# 4__Output_Feedback_2.net
KiCad netlist of a schematic drawn in Altium Designer
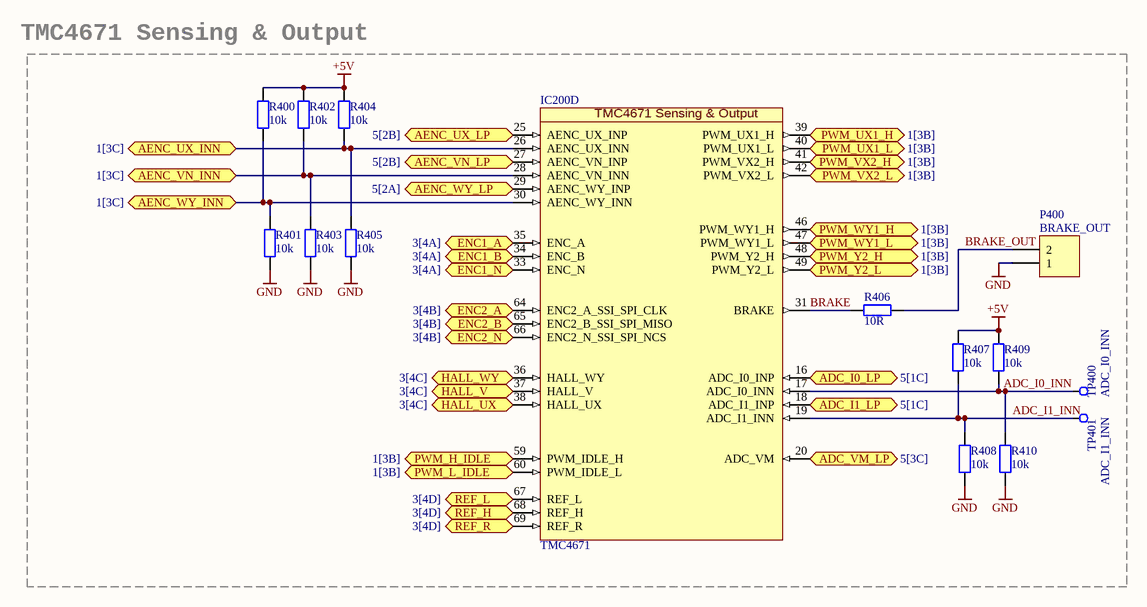
[diagram p0: [4]_Output_Feedback_2.SchDoc]

(export (version "E")
  (design (tool "Eeschema 10.0.6"))
  (components
    (comp (ref "IC200")
      (value "TMC4671")
      (footprint "QFN40P1050X650X90_HS-77N")
      (fields (field (name "MF") "TRINAMIC"))
      (libsource (lib "TMC4671-EVAL_V1_0") (part "TMC4671"))
    )
    (comp (ref "P400")
      (value "BRAKE_OUT")
      (footprint "TH_HDR_1X2")
      (description "Header, 2-Pin")
      (libsource (lib "Miscellaneous Connectors") (part "Header 2"))
    )
    (comp (ref "R400")
      (value "10k")
      (footprint "R0603")
      (description "SMD Chip Resistor, Thick Film, 10 kohm, 50 V, 0603 [1608 Metric], 63 mW, ± 1%, MC Series")
      (fields
        (field (name "MPN") "MC0063W0603110K")
        (field (name "MF") "MULTICOMP")
        (field (name "RESISTANCE") "10k")
      )
      (libsource (lib "SMD_Passives") (part "R, 10 kohm, 50 V, 0603 [1608 Metric], 63 mW, ± 1%, MC Series"))
    )
    (comp (ref "R401")
      (value "10k")
      (footprint "R0603")
      (description "SMD Chip Resistor, Thick Film, 10 kohm, 50 V, 0603 [1608 Metric], 63 mW, ± 1%, MC Series")
      (fields
        (field (name "MPN") "MC0063W0603110K")
        (field (name "MF") "MULTICOMP")
        (field (name "RESISTANCE") "10k")
      )
      (libsource (lib "SMD_Passives") (part "R, 10 kohm, 50 V, 0603 [1608 Metric], 63 mW, ± 1%, MC Series"))
    )
    (comp (ref "R402")
      (value "10k")
      (footprint "R0603")
      (description "SMD Chip Resistor, Thick Film, 10 kohm, 50 V, 0603 [1608 Metric], 63 mW, ± 1%, MC Series")
      (fields
        (field (name "MPN") "MC0063W0603110K")
        (field (name "MF") "MULTICOMP")
        (field (name "RESISTANCE") "10k")
      )
      (libsource (lib "SMD_Passives") (part "R, 10 kohm, 50 V, 0603 [1608 Metric], 63 mW, ± 1%, MC Series"))
    )
    (comp (ref "R403")
      (value "10k")
      (footprint "R0603")
      (description "SMD Chip Resistor, Thick Film, 10 kohm, 50 V, 0603 [1608 Metric], 63 mW, ± 1%, MC Series")
      (fields
        (field (name "MPN") "MC0063W0603110K")
        (field (name "MF") "MULTICOMP")
        (field (name "RESISTANCE") "10k")
      )
      (libsource (lib "SMD_Passives") (part "R, 10 kohm, 50 V, 0603 [1608 Metric], 63 mW, ± 1%, MC Series"))
    )
    (comp (ref "R404")
      (value "10k")
      (footprint "R0603")
      (description "SMD Chip Resistor, Thick Film, 10 kohm, 50 V, 0603 [1608 Metric], 63 mW, ± 1%, MC Series")
      (fields
        (field (name "MPN") "MC0063W0603110K")
        (field (name "MF") "MULTICOMP")
        (field (name "RESISTANCE") "10k")
      )
      (libsource (lib "SMD_Passives") (part "R, 10 kohm, 50 V, 0603 [1608 Metric], 63 mW, ± 1%, MC Series"))
    )
    (comp (ref "R405")
      (value "10k")
      (footprint "R0603")
      (description "SMD Chip Resistor, Thick Film, 10 kohm, 50 V, 0603 [1608 Metric], 63 mW, ± 1%, MC Series")
      (fields
        (field (name "MPN") "MC0063W0603110K")
        (field (name "MF") "MULTICOMP")
        (field (name "RESISTANCE") "10k")
      )
      (libsource (lib "SMD_Passives") (part "R, 10 kohm, 50 V, 0603 [1608 Metric], 63 mW, ± 1%, MC Series"))
    )
    (comp (ref "R406")
      (value "10R")
      (footprint "R0603")
      (description "SMD Chip Resistor, Thick Film, 10 ohm, 50 V, 0603 [1608 Metric], 100 mW, ± 1%, MCWR Series")
      (fields
        (field (name "MPN") "MC0063W0603110K")
        (field (name "MF") "MULTICOMP")
        (field (name "RESISTANCE") "10R")
      )
      (libsource (lib "SMD_Passives") (part "R, 10 ohm, 50 V, 0603 [1608 Metric], 100 mW, ± 1%, MCWR Series"))
    )
    (comp (ref "R407")
      (value "10k")
      (footprint "R0603")
      (description "SMD Chip Resistor, Thick Film, 10 kohm, 50 V, 0603 [1608 Metric], 63 mW, ± 1%, MC Series")
      (fields
        (field (name "MPN") "MC0063W0603110K")
        (field (name "MF") "MULTICOMP")
        (field (name "RESISTANCE") "10k")
      )
      (libsource (lib "SMD_Passives") (part "R, 10 kohm, 50 V, 0603 [1608 Metric], 63 mW, ± 1%, MC Series"))
    )
    (comp (ref "R408")
      (value "10k")
      (footprint "R0603")
      (description "SMD Chip Resistor, Thick Film, 10 kohm, 50 V, 0603 [1608 Metric], 63 mW, ± 1%, MC Series")
      (fields
        (field (name "MPN") "MC0063W0603110K")
        (field (name "MF") "MULTICOMP")
        (field (name "RESISTANCE") "10k")
      )
      (libsource (lib "SMD_Passives") (part "R, 10 kohm, 50 V, 0603 [1608 Metric], 63 mW, ± 1%, MC Series"))
    )
    (comp (ref "R409")
      (value "10k")
      (footprint "R0603")
      (description "SMD Chip Resistor, Thick Film, 10 kohm, 50 V, 0603 [1608 Metric], 63 mW, ± 1%, MC Series")
      (fields
        (field (name "MPN") "MC0063W0603110K")
        (field (name "MF") "MULTICOMP")
        (field (name "RESISTANCE") "10k")
      )
      (libsource (lib "SMD_Passives") (part "R, 10 kohm, 50 V, 0603 [1608 Metric], 63 mW, ± 1%, MC Series"))
    )
    (comp (ref "R410")
      (value "10k")
      (footprint "R0603")
      (description "SMD Chip Resistor, Thick Film, 10 kohm, 50 V, 0603 [1608 Metric], 63 mW, ± 1%, MC Series")
      (fields
        (field (name "MPN") "MC0063W0603110K")
        (field (name "MF") "MULTICOMP")
        (field (name "RESISTANCE") "10k")
      )
      (libsource (lib "SMD_Passives") (part "R, 10 kohm, 50 V, 0603 [1608 Metric], 63 mW, ± 1%, MC Series"))
    )
    (comp (ref "TP400")
      (value "ADC_I0_INN")
      (footprint "TP_SMD_1.2MM_ROUND")
      (description "SMD testpoint, 1.2mm pad, round")
      (libsource (lib "TMC-EVAL_TMPL_V1_0") (part "TP_SMD_Xmm"))
    )
    (comp (ref "TP401")
      (value "ADC_I1_INN")
      (footprint "TP_SMD_1.2MM_ROUND")
      (description "SMD testpoint, 1.2mm pad, round")
      (libsource (lib "TMC-EVAL_TMPL_V1_0") (part "TP_SMD_Xmm"))
    )
  )
  (nets
    (net (code "1") (name "+5V") (class "Default")
      (node (ref "R400") (pin "2") (pinfunction "2_2") (pintype "passive"))
      (node (ref "R402") (pin "2") (pinfunction "2_2") (pintype "passive"))
      (node (ref "R404") (pin "2") (pinfunction "2_2") (pintype "passive"))
      (node (ref "R407") (pin "2") (pinfunction "2_2") (pintype "passive"))
      (node (ref "R409") (pin "2") (pinfunction "2_2") (pintype "passive"))
    )
    (net (code "2") (name "/ADC_I0_INN") (class "Default")
      (node (ref "IC200") (pin "17") (pinfunction "ADC_I0_INN_17") (pintype "input"))
      (node (ref "R409") (pin "1") (pinfunction "1_1") (pintype "passive"))
      (node (ref "R410") (pin "2") (pinfunction "2_2") (pintype "passive"))
      (node (ref "TP400") (pin "1") (pinfunction "1_1") (pintype "passive"))
    )
    (net (code "3") (name "/ADC_I0_LP") (class "Default")
      (node (ref "IC200") (pin "16") (pinfunction "ADC_I0_INP_16") (pintype "input"))
    )
    (net (code "4") (name "/ADC_I1_INN") (class "Default")
      (node (ref "IC200") (pin "19") (pinfunction "ADC_I1_INN_19") (pintype "input"))
      (node (ref "R407") (pin "1") (pinfunction "1_1") (pintype "passive"))
      (node (ref "R408") (pin "2") (pinfunction "2_2") (pintype "passive"))
      (node (ref "TP401") (pin "1") (pinfunction "1_1") (pintype "passive"))
    )
    (net (code "5") (name "/ADC_I1_LP") (class "Default")
      (node (ref "IC200") (pin "18") (pinfunction "ADC_I1_INP_18") (pintype "input"))
    )
    (net (code "6") (name "/ADC_VM_LP") (class "Default")
      (node (ref "IC200") (pin "20") (pinfunction "ADC_VM_20") (pintype "input"))
    )
    (net (code "7") (name "/AENC_UX_INN") (class "Default")
      (node (ref "IC200") (pin "26") (pinfunction "AENC_UX_INN_26") (pintype "input"))
      (node (ref "R404") (pin "1") (pinfunction "1_1") (pintype "passive"))
      (node (ref "R405") (pin "2") (pinfunction "2_2") (pintype "passive"))
    )
    (net (code "8") (name "/AENC_UX_LP") (class "Default")
      (node (ref "IC200") (pin "25") (pinfunction "AENC_UX_INP_25") (pintype "input"))
    )
    (net (code "9") (name "/AENC_VN_INN") (class "Default")
      (node (ref "IC200") (pin "28") (pinfunction "AENC_VN_INN_28") (pintype "input"))
      (node (ref "R402") (pin "1") (pinfunction "1_1") (pintype "passive"))
      (node (ref "R403") (pin "2") (pinfunction "2_2") (pintype "passive"))
    )
    (net (code "10") (name "/AENC_VN_LP") (class "Default")
      (node (ref "IC200") (pin "27") (pinfunction "AENC_VN_INP_27") (pintype "input"))
    )
    (net (code "11") (name "/AENC_WY_INN") (class "Default")
      (node (ref "IC200") (pin "30") (pinfunction "AENC_WY_INN_30") (pintype "input"))
      (node (ref "R400") (pin "1") (pinfunction "1_1") (pintype "passive"))
      (node (ref "R401") (pin "2") (pinfunction "2_2") (pintype "passive"))
    )
    (net (code "12") (name "/AENC_WY_LP") (class "Default")
      (node (ref "IC200") (pin "29") (pinfunction "AENC_WY_INP_29") (pintype "input"))
    )
    (net (code "13") (name "/BRAKE") (class "Default")
      (node (ref "IC200") (pin "31") (pinfunction "BRAKE_31") (pintype "output"))
      (node (ref "R406") (pin "2") (pinfunction "2_2") (pintype "passive"))
    )
    (net (code "14") (name "/BRAKE_OUT") (class "Default")
      (node (ref "P400") (pin "2") (pinfunction "2_2") (pintype "passive"))
      (node (ref "R406") (pin "1") (pinfunction "1_1") (pintype "passive"))
    )
    (net (code "15") (name "/ENC1_A") (class "Default")
      (node (ref "IC200") (pin "35") (pinfunction "ENC_A_35") (pintype "input"))
    )
    (net (code "16") (name "/ENC1_B") (class "Default")
      (node (ref "IC200") (pin "34") (pinfunction "ENC_B_34") (pintype "input"))
    )
    (net (code "17") (name "/ENC1_N") (class "Default")
      (node (ref "IC200") (pin "33") (pinfunction "ENC_N_33") (pintype "input"))
    )
    (net (code "18") (name "/ENC2_A") (class "Default")
      (node (ref "IC200") (pin "64") (pinfunction "ENC2_A_SSI_SPI_CLK_64") (pintype "input"))
    )
    (net (code "19") (name "/ENC2_B") (class "Default")
      (node (ref "IC200") (pin "65") (pinfunction "ENC2_B_SSI_SPI_MISO_65") (pintype "input"))
    )
    (net (code "20") (name "/ENC2_N") (class "Default")
      (node (ref "IC200") (pin "66") (pinfunction "ENC2_N_SSI_SPI_NCS_66") (pintype "input"))
    )
    (net (code "21") (name "/HALL_UX") (class "Default")
      (node (ref "IC200") (pin "38") (pinfunction "HALL_UX_38") (pintype "input"))
    )
    (net (code "22") (name "/HALL_V") (class "Default")
      (node (ref "IC200") (pin "37") (pinfunction "HALL_V_37") (pintype "input"))
    )
    (net (code "23") (name "/HALL_WY") (class "Default")
      (node (ref "IC200") (pin "36") (pinfunction "HALL_WY_36") (pintype "input"))
    )
    (net (code "24") (name "/PWM_H_IDLE") (class "Default")
      (node (ref "IC200") (pin "59") (pinfunction "PWM_IDLE_H_59") (pintype "input"))
    )
    (net (code "25") (name "/PWM_L_IDLE") (class "Default")
      (node (ref "IC200") (pin "60") (pinfunction "PWM_IDLE_L_60") (pintype "input"))
    )
    (net (code "26") (name "/PWM_UX1_H") (class "Default")
      (node (ref "IC200") (pin "39") (pinfunction "PWM_UX1_H_39") (pintype "output"))
    )
    (net (code "27") (name "/PWM_UX1_L") (class "Default")
      (node (ref "IC200") (pin "40") (pinfunction "PWM_UX1_L_40") (pintype "output"))
    )
    (net (code "28") (name "/PWM_VX2_H") (class "Default")
      (node (ref "IC200") (pin "41") (pinfunction "PWM_VX2_H_41") (pintype "output"))
    )
    (net (code "29") (name "/PWM_VX2_L") (class "Default")
      (node (ref "IC200") (pin "42") (pinfunction "PWM_VX2_L_42") (pintype "output"))
    )
    (net (code "30") (name "/PWM_WY1_H") (class "Default")
      (node (ref "IC200") (pin "46") (pinfunction "PWM_WY1_H_46") (pintype "output"))
    )
    (net (code "31") (name "/PWM_WY1_L") (class "Default")
      (node (ref "IC200") (pin "47") (pinfunction "PWM_WY1_L_47") (pintype "output"))
    )
    (net (code "32") (name "/PWM_Y2_H") (class "Default")
      (node (ref "IC200") (pin "48") (pinfunction "PWM_Y2_H_48") (pintype "output"))
    )
    (net (code "33") (name "/PWM_Y2_L") (class "Default")
      (node (ref "IC200") (pin "49") (pinfunction "PWM_Y2_L_49") (pintype "output"))
    )
    (net (code "34") (name "/REF_H") (class "Default")
      (node (ref "IC200") (pin "68") (pinfunction "REF_H_68") (pintype "input"))
    )
    (net (code "35") (name "/REF_L") (class "Default")
      (node (ref "IC200") (pin "67") (pinfunction "REF_L_67") (pintype "input"))
    )
    (net (code "36") (name "/REF_R") (class "Default")
      (node (ref "IC200") (pin "69") (pinfunction "REF_R_69") (pintype "input"))
    )
    (net (code "37") (name "GND") (class "Default")
      (node (ref "P400") (pin "1") (pinfunction "1_1") (pintype "passive"))
      (node (ref "R401") (pin "1") (pinfunction "1_1") (pintype "passive"))
      (node (ref "R403") (pin "1") (pinfunction "1_1") (pintype "passive"))
      (node (ref "R405") (pin "1") (pinfunction "1_1") (pintype "passive"))
      (node (ref "R408") (pin "1") (pinfunction "1_1") (pintype "passive"))
      (node (ref "R410") (pin "1") (pinfunction "1_1") (pintype "passive"))
    )
  )
)
